# Power_PMIC.net
KiCad netlist of a schematic drawn in Altium Designer
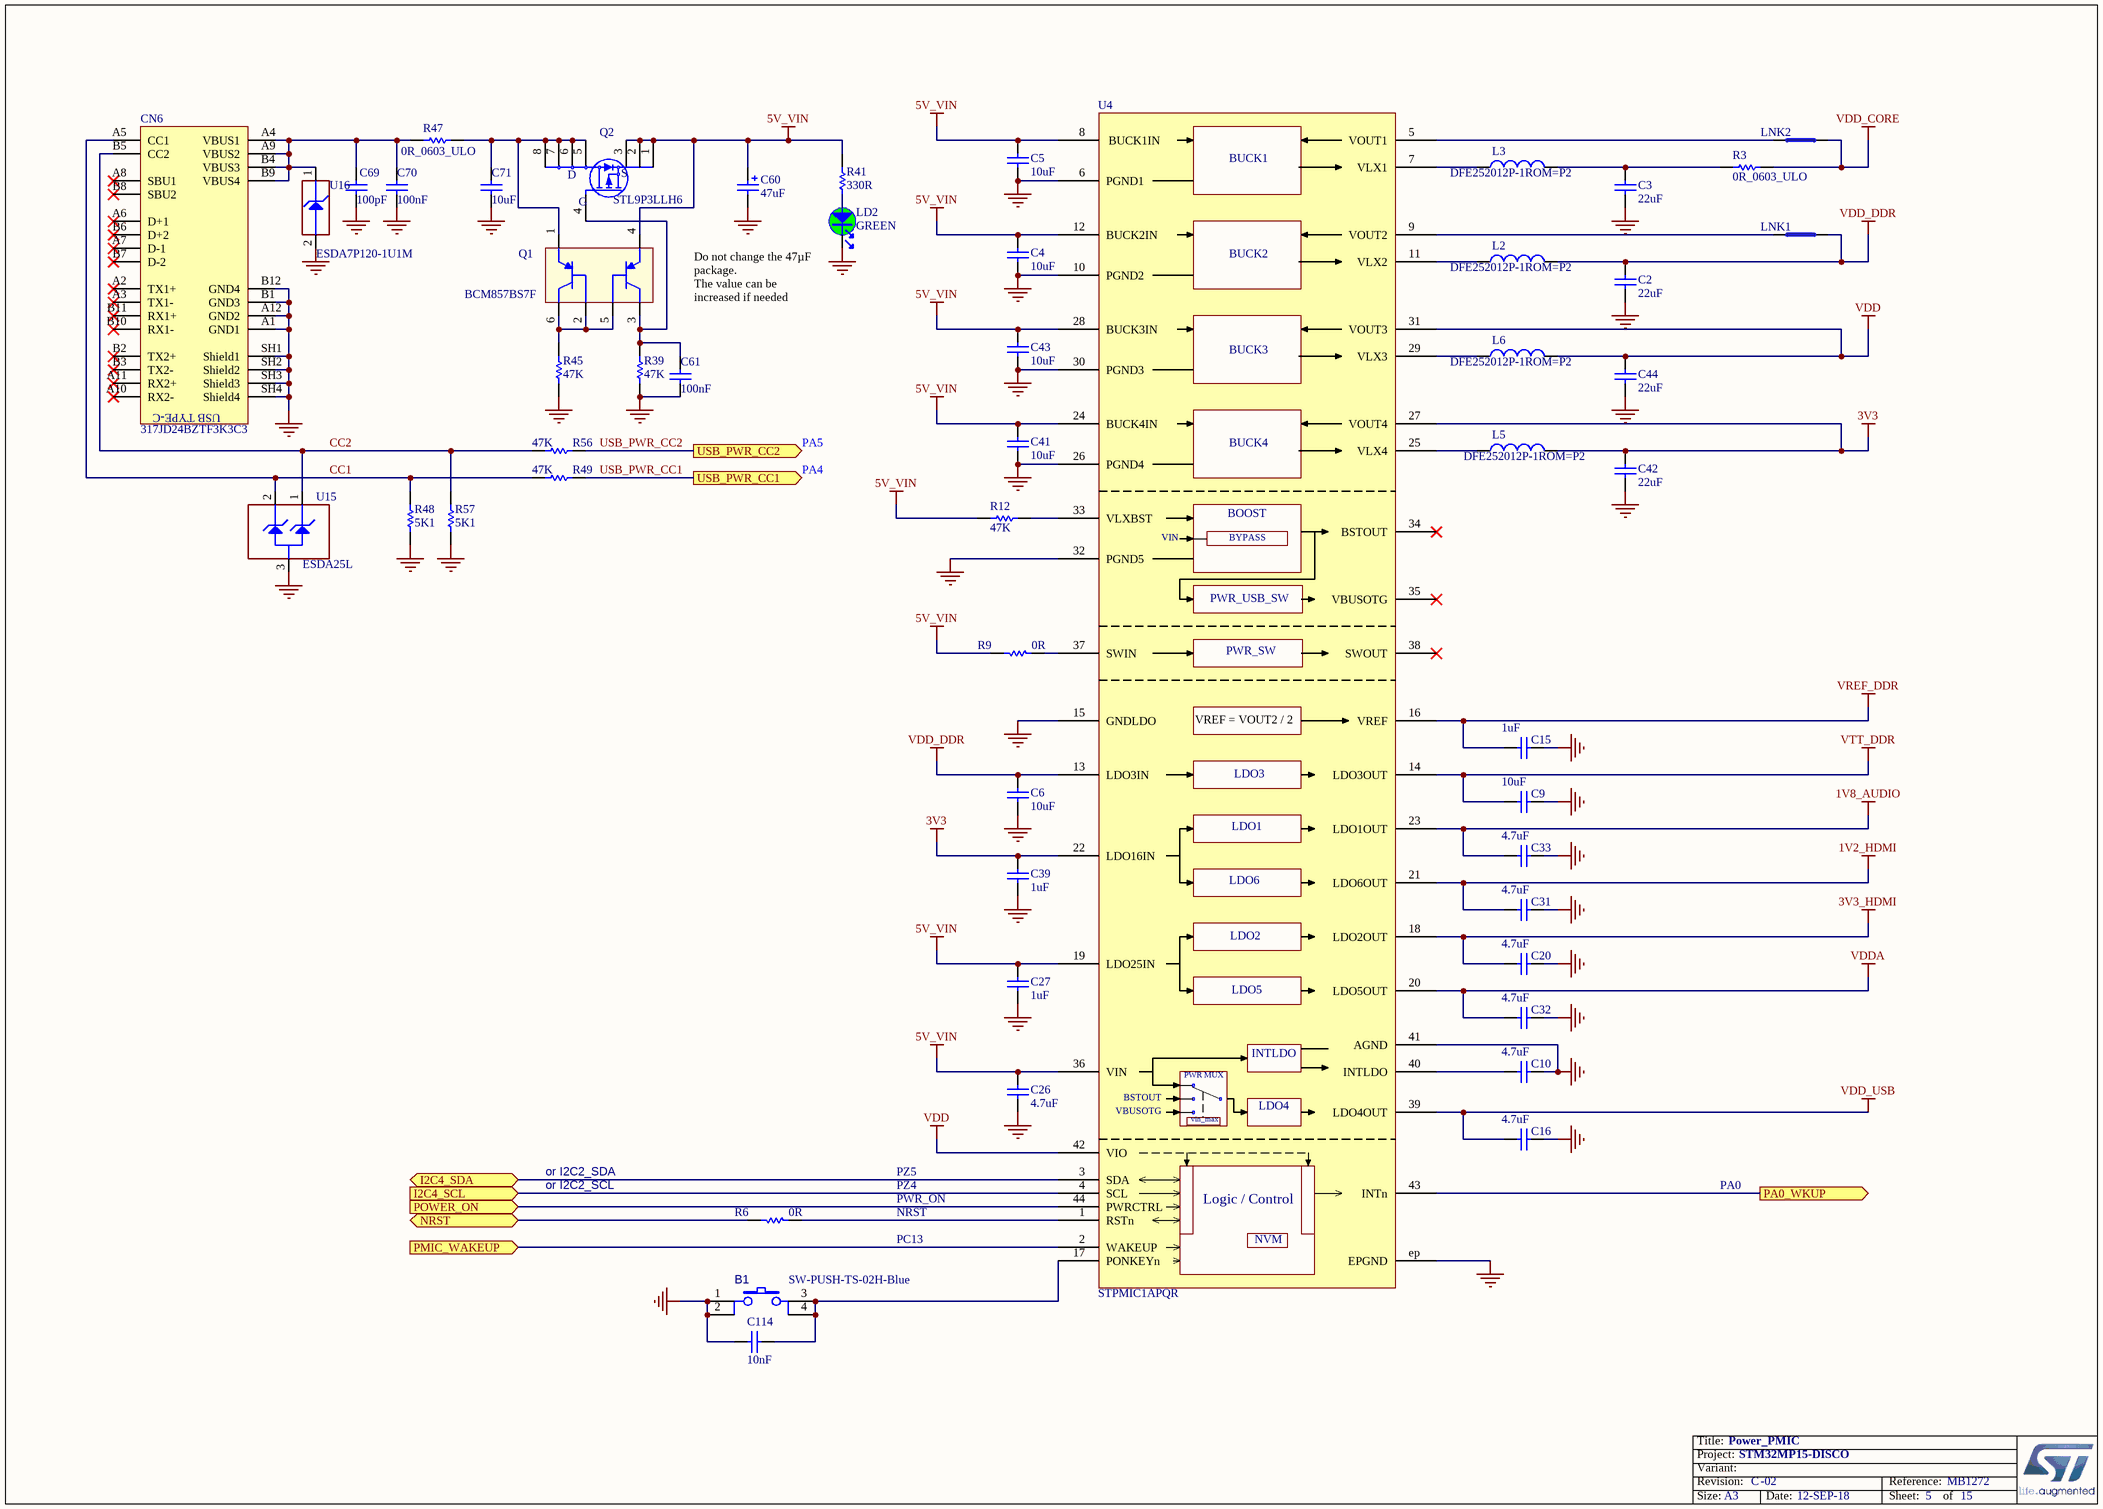
[diagram p0: Power_PMIC.SchDoc]

(export (version "E")
  (design (tool "Eeschema 10.0.6"))
  (components
    (comp (ref "B1")
      (value "SW-PUSH-TS-02H-Blue")
      (footprint "SWI_JIUBABA_C-TS-02H-2-5-B-V-T_R_BLUE")
      (description "Switch HW SMD blue")
      (fields
        (field (name "INTERNAL_PART_NUMBER") "MCD-00172")
        (field (name "MANUFACTURER_PART_NUMBER") "C-TS-02H-2.5-B-V-T/R BLUE")
        (field (name "PROVIDED_BY") "SUBCO")
      )
      (libsource (lib "MCD_PARTS_database") (part "SW-PUSH-TS-02H-Blue"))
    )
    (comp (ref "C2")
      (value "22uF")
      (footprint "C0603")
      (description "Capacitor, MLCC, 22uF, 6V3, X5R, 20%, 0603, T=0,8mm")
      (fields
        (field (name "INTERNAL_PART_NUMBER") "MCD-00100")
        (field (name "MANUFACTURER_PART_NUMBER") "GRM188R60J226MEA0J")
        (field (name "PROVIDED_BY") "SUBCO")
      )
      (libsource (lib "MCD_PARTS_database") (part "Capacitor"))
    )
    (comp (ref "C3")
      (value "22uF")
      (footprint "C0603")
      (description "Capacitor, MLCC, 22uF, 6V3, X5R, 20%, 0603, T=0,8mm")
      (fields
        (field (name "INTERNAL_PART_NUMBER") "MCD-00100")
        (field (name "MANUFACTURER_PART_NUMBER") "GRM188R60J226MEA0J")
        (field (name "PROVIDED_BY") "SUBCO")
      )
      (libsource (lib "MCD_PARTS_database") (part "Capacitor"))
    )
    (comp (ref "C4")
      (value "10uF")
      (footprint "C0603")
      (description "Capacitor, MLCC, 10uF, 10V, X5R, 10%, 0603, T=0,8mm")
      (fields
        (field (name "INTERNAL_PART_NUMBER") "MCD-00099")
        (field (name "MANUFACTURER_PART_NUMBER") "GRM188R61A106KE69D")
        (field (name "PROVIDED_BY") "SUBCO")
      )
      (libsource (lib "MCD_PARTS_database") (part "Capacitor"))
    )
    (comp (ref "C5")
      (value "10uF")
      (footprint "C0603")
      (description "Capacitor, MLCC, 10uF, 10V, X5R, 10%, 0603, T=0,8mm")
      (fields
        (field (name "INTERNAL_PART_NUMBER") "MCD-00099")
        (field (name "MANUFACTURER_PART_NUMBER") "GRM188R61A106KE69D")
        (field (name "PROVIDED_BY") "SUBCO")
      )
      (libsource (lib "MCD_PARTS_database") (part "Capacitor"))
    )
    (comp (ref "C6")
      (value "10uF")
      (footprint "C0603")
      (description "Capacitor, MLCC, 10uF, 10V, X5R, 10%, 0603, T=0,8mm")
      (fields
        (field (name "INTERNAL_PART_NUMBER") "MCD-00099")
        (field (name "MANUFACTURER_PART_NUMBER") "GRM188R61A106KE69D")
        (field (name "PROVIDED_BY") "SUBCO")
      )
      (libsource (lib "MCD_PARTS_database") (part "Capacitor"))
    )
    (comp (ref "C9")
      (value "10uF")
      (footprint "C0603")
      (description "Capacitor, MLCC, 10uF, 10V, X5R, 10%, 0603, T=0,8mm")
      (fields
        (field (name "INTERNAL_PART_NUMBER") "MCD-00099")
        (field (name "MANUFACTURER_PART_NUMBER") "GRM188R61A106KE69D")
        (field (name "PROVIDED_BY") "SUBCO")
      )
      (libsource (lib "MCD_PARTS_database") (part "Capacitor"))
    )
    (comp (ref "C10")
      (value "4.7uF")
      (footprint "C0402")
      (description "Capacitor, MLCC, 4.7uF, 6V3, X5R, 20%, 0402, T=0,5mm")
      (fields
        (field (name "INTERNAL_PART_NUMBER") "MCD-01356")
        (field (name "MANUFACTURER_PART_NUMBER") "GRM155R60J475ME47")
        (field (name "PROVIDED_BY") "SUBCO")
      )
      (libsource (lib "MCD_PARTS_database") (part "Capacitor"))
    )
    (comp (ref "C15")
      (value "1uF")
      (footprint "C0402")
      (description "Capacitor, MLCC, 1uF, 6V3, X5R, 10%, 0402, T=0,5mm")
      (fields
        (field (name "INTERNAL_PART_NUMBER") "MCD-00095")
        (field (name "MANUFACTURER_PART_NUMBER") "GRM155R61E105KA12")
        (field (name "PROVIDED_BY") "SUBCO")
      )
      (libsource (lib "MCD_PARTS_database") (part "Capacitor"))
    )
    (comp (ref "C16")
      (value "4.7uF")
      (footprint "C0402")
      (description "Capacitor, MLCC, 4.7uF, 6V3, X5R, 20%, 0402, T=0,5mm")
      (fields
        (field (name "INTERNAL_PART_NUMBER") "MCD-01356")
        (field (name "MANUFACTURER_PART_NUMBER") "GRM155R60J475ME47")
        (field (name "PROVIDED_BY") "SUBCO")
      )
      (libsource (lib "MCD_PARTS_database") (part "Capacitor"))
    )
    (comp (ref "C20")
      (value "4.7uF")
      (footprint "C0402")
      (description "Capacitor, MLCC, 4.7uF, 6V3, X5R, 20%, 0402, T=0,5mm")
      (fields
        (field (name "INTERNAL_PART_NUMBER") "MCD-01356")
        (field (name "MANUFACTURER_PART_NUMBER") "GRM155R60J475ME47")
        (field (name "PROVIDED_BY") "SUBCO")
      )
      (libsource (lib "MCD_PARTS_database") (part "Capacitor"))
    )
    (comp (ref "C26")
      (value "4.7uF")
      (footprint "C0402")
      (description "Capacitor, MLCC, 4.7uF, 6V3, X5R, 20%, 0402, T=0,5mm")
      (fields
        (field (name "INTERNAL_PART_NUMBER") "MCD-01356")
        (field (name "MANUFACTURER_PART_NUMBER") "GRM155R60J475ME47")
        (field (name "PROVIDED_BY") "SUBCO")
      )
      (libsource (lib "MCD_PARTS_database") (part "Capacitor"))
    )
    (comp (ref "C27")
      (value "1uF")
      (footprint "C0402")
      (description "Capacitor, MLCC, 1uF, 6V3, X5R, 10%, 0402, T=0,5mm")
      (fields
        (field (name "INTERNAL_PART_NUMBER") "MCD-00095")
        (field (name "MANUFACTURER_PART_NUMBER") "GRM155R61E105KA12")
        (field (name "PROVIDED_BY") "SUBCO")
      )
      (libsource (lib "MCD_PARTS_database") (part "Capacitor"))
    )
    (comp (ref "C31")
      (value "4.7uF")
      (footprint "C0402")
      (description "Capacitor, MLCC, 4.7uF, 6V3, X5R, 20%, 0402, T=0,5mm")
      (fields
        (field (name "INTERNAL_PART_NUMBER") "MCD-01356")
        (field (name "MANUFACTURER_PART_NUMBER") "GRM155R60J475ME47")
        (field (name "PROVIDED_BY") "SUBCO")
      )
      (libsource (lib "MCD_PARTS_database") (part "Capacitor"))
    )
    (comp (ref "C32")
      (value "4.7uF")
      (footprint "C0402")
      (description "Capacitor, MLCC, 4.7uF, 6V3, X5R, 20%, 0402, T=0,5mm")
      (fields
        (field (name "INTERNAL_PART_NUMBER") "MCD-01356")
        (field (name "MANUFACTURER_PART_NUMBER") "GRM155R60J475ME47")
        (field (name "PROVIDED_BY") "SUBCO")
      )
      (libsource (lib "MCD_PARTS_database") (part "Capacitor"))
    )
    (comp (ref "C33")
      (value "4.7uF")
      (footprint "C0402")
      (description "Capacitor, MLCC, 4.7uF, 6V3, X5R, 20%, 0402, T=0,5mm")
      (fields
        (field (name "INTERNAL_PART_NUMBER") "MCD-01356")
        (field (name "MANUFACTURER_PART_NUMBER") "GRM155R60J475ME47")
        (field (name "PROVIDED_BY") "SUBCO")
      )
      (libsource (lib "MCD_PARTS_database") (part "Capacitor"))
    )
    (comp (ref "C39")
      (value "1uF")
      (footprint "C0402")
      (description "Capacitor, MLCC, 1uF, 6V3, X5R, 10%, 0402, T=0,5mm")
      (fields
        (field (name "INTERNAL_PART_NUMBER") "MCD-00095")
        (field (name "MANUFACTURER_PART_NUMBER") "GRM155R61E105KA12")
        (field (name "PROVIDED_BY") "SUBCO")
      )
      (libsource (lib "MCD_PARTS_database") (part "Capacitor"))
    )
    (comp (ref "C41")
      (value "10uF")
      (footprint "C0603")
      (description "Capacitor, MLCC, 10uF, 10V, X5R, 10%, 0603, T=0,8mm")
      (fields
        (field (name "INTERNAL_PART_NUMBER") "MCD-00099")
        (field (name "MANUFACTURER_PART_NUMBER") "GRM188R61A106KE69D")
        (field (name "PROVIDED_BY") "SUBCO")
      )
      (libsource (lib "MCD_PARTS_database") (part "Capacitor"))
    )
    (comp (ref "C42")
      (value "22uF")
      (footprint "C0603")
      (description "Capacitor, MLCC, 22uF, 6V3, X5R, 20%, 0603, T=0,8mm")
      (fields
        (field (name "INTERNAL_PART_NUMBER") "MCD-00100")
        (field (name "MANUFACTURER_PART_NUMBER") "GRM188R60J226MEA0J")
        (field (name "PROVIDED_BY") "SUBCO")
      )
      (libsource (lib "MCD_PARTS_database") (part "Capacitor"))
    )
    (comp (ref "C43")
      (value "10uF")
      (footprint "C0603")
      (description "Capacitor, MLCC, 10uF, 10V, X5R, 10%, 0603, T=0,8mm")
      (fields
        (field (name "INTERNAL_PART_NUMBER") "MCD-00099")
        (field (name "MANUFACTURER_PART_NUMBER") "GRM188R61A106KE69D")
        (field (name "PROVIDED_BY") "SUBCO")
      )
      (libsource (lib "MCD_PARTS_database") (part "Capacitor"))
    )
    (comp (ref "C44")
      (value "22uF")
      (footprint "C0603")
      (description "Capacitor, MLCC, 22uF, 6V3, X5R, 20%, 0603, T=0,8mm")
      (fields
        (field (name "INTERNAL_PART_NUMBER") "MCD-00100")
        (field (name "MANUFACTURER_PART_NUMBER") "GRM188R60J226MEA0J")
        (field (name "PROVIDED_BY") "SUBCO")
      )
      (libsource (lib "MCD_PARTS_database") (part "Capacitor"))
    )
    (comp (ref "C60")
      (value "47uF")
      (footprint "CPOL_TAJ-C_2312_H2P6")
      (description "Capacitor, Tantalum, 47uF, 16V, 10%, TypeC")
      (fields
        (field (name "INTERNAL_PART_NUMBER") "MCD-00559")
        (field (name "MANUFACTURER_PART_NUMBER") "TAJC476K016RNJ")
        (field (name "PROVIDED_BY") "SUBCO")
      )
      (libsource (lib "MCD_PARTS_database") (part "Cap_POL_TANA"))
    )
    (comp (ref "C61")
      (value "100nF")
      (footprint "C0402")
      (description "Capacitor,100nF,16V,X7R,10%,0402")
      (fields
        (field (name "INTERNAL_PART_NUMBER") "MCD-00006")
        (field (name "MANUFACTURER_PART_NUMBER") "CC0402KRX7R7BB104")
        (field (name "PROVIDED_BY") "SUBCO")
      )
      (libsource (lib "MCD_PARTS_database") (part "Capacitor"))
    )
    (comp (ref "C69")
      (value "100pF")
      (footprint "C0402")
      (description "Capacitor, MLCC, 100pF, 50V, NPO, 5%, 0402, T=0,5mm")
      (fields
        (field (name "INTERNAL_PART_NUMBER") "MCD-00205")
        (field (name "MANUFACTURER_PART_NUMBER") "CC0402JRNPO9BN101")
        (field (name "PROVIDED_BY") "SUBCO")
      )
      (libsource (lib "MCD_PARTS_database") (part "Capacitor"))
    )
    (comp (ref "C70")
      (value "100nF")
      (footprint "C0402")
      (description "Capacitor,100nF,16V,X7R,10%,0402")
      (fields
        (field (name "INTERNAL_PART_NUMBER") "MCD-00006")
        (field (name "MANUFACTURER_PART_NUMBER") "CC0402KRX7R7BB104")
        (field (name "PROVIDED_BY") "SUBCO")
      )
      (libsource (lib "MCD_PARTS_database") (part "Capacitor"))
    )
    (comp (ref "C71")
      (value "10uF")
      (footprint "C0805")
      (description "Capacitor, MLCC, 10uF, 25V, X5R, 10%, 0805, T=0,85mm")
      (fields
        (field (name "INTERNAL_PART_NUMBER") "MCD-00014")
        (field (name "MANUFACTURER_PART_NUMBER") "CC0805KRX5R8BB106")
        (field (name "PROVIDED_BY") "SUBCO")
      )
      (libsource (lib "MCD_PARTS_database") (part "Capacitor"))
    )
    (comp (ref "C114")
      (value "10nF")
      (footprint "C0402")
      (description "Capacitor, MLCC, 10nF, 16V, X7R, 10%, 0402, T=0.5mm")
      (fields
        (field (name "INTERNAL_PART_NUMBER") "MCD-00011")
        (field (name "MANUFACTURER_PART_NUMBER") "CC0402KRX7R7BB103")
        (field (name "PROVIDED_BY") "SUBCO")
      )
      (libsource (lib "MCD_PARTS_database") (part "Capacitor"))
    )
    (comp (ref "CN6")
      (value "317JD24BZTF3K3C3")
      (footprint "CON_USB-TYPEC_COXOC_317JD24BZTF3K3C3")
      (description "USB tyce C certified receptacle for 1.6mm pcb height")
      (fields
        (field (name "INTERNAL_PART_NUMBER") "MCD-01108")
        (field (name "MANUFACTURER") "CHANT SINCERE (COXOC)")
        (field (name "PROVIDED_BY") "SUBCO")
      )
      (libsource (lib "MCD_PARTS_database") (part "USB_TYPE_C_Receptacle_317JD24BZTF3K3C3"))
    )
    (comp (ref "L2")
      (value "IND_1uH_42mohm_3.2A")
      (footprint "IND_2520_TOKO_DFE252012P")
      (description "Power Inductor ,1µH,4.3A max,+-20%,0.042ohm,2520")
      (fields
        (field (name "INTERNAL_PART_NUMBER") "MCD-01122")
        (field (name "MANUFACTURER_PART_NUMBER") "DFE252012P-1ROM=P2")
        (field (name "MANUFACTURER") "MURATA")
        (field (name "PROVIDED_BY") "SUBCO")
      )
      (libsource (lib "MCD_PARTS_database") (part "IND_1uH_42mohm_3.2A"))
    )
    (comp (ref "L3")
      (value "IND_1uH_42mohm_3.2A")
      (footprint "IND_2520_TOKO_DFE252012P")
      (description "Power Inductor ,1µH,4.3A max,+-20%,0.042ohm,2520")
      (fields
        (field (name "INTERNAL_PART_NUMBER") "MCD-01122")
        (field (name "MANUFACTURER_PART_NUMBER") "DFE252012P-1ROM=P2")
        (field (name "MANUFACTURER") "MURATA")
        (field (name "PROVIDED_BY") "SUBCO")
      )
      (libsource (lib "MCD_PARTS_database") (part "IND_1uH_42mohm_3.2A"))
    )
    (comp (ref "L5")
      (value "IND_1uH_42mohm_3.2A")
      (footprint "IND_2520_TOKO_DFE252012P")
      (description "Power Inductor ,1µH,4.3A max,+-20%,0.042ohm,2520")
      (fields
        (field (name "INTERNAL_PART_NUMBER") "MCD-01122")
        (field (name "MANUFACTURER_PART_NUMBER") "DFE252012P-1ROM=P2")
        (field (name "MANUFACTURER") "MURATA")
        (field (name "PROVIDED_BY") "SUBCO")
      )
      (libsource (lib "MCD_PARTS_database") (part "IND_1uH_42mohm_3.2A"))
    )
    (comp (ref "L6")
      (value "IND_1uH_42mohm_3.2A")
      (footprint "IND_2520_TOKO_DFE252012P")
      (description "Power Inductor ,1µH,4.3A max,+-20%,0.042ohm,2520")
      (fields
        (field (name "INTERNAL_PART_NUMBER") "MCD-01122")
        (field (name "MANUFACTURER_PART_NUMBER") "DFE252012P-1ROM=P2")
        (field (name "MANUFACTURER") "MURATA")
        (field (name "PROVIDED_BY") "SUBCO")
      )
      (libsource (lib "MCD_PARTS_database") (part "IND_1uH_42mohm_3.2A"))
    )
    (comp (ref "LD2")
      (value "GREEN")
      (footprint "LED_0603_GREEN")
      (description "LED, Green, 0603")
      (fields
        (field (name "INTERNAL_PART_NUMBER") "MCD-00050")
        (field (name "MANUFACTURER_PART_NUMBER") "19-213SYGC/S530-E2/TR8")
        (field (name "PROVIDED_BY") "SUBCO")
      )
      (libsource (lib "MCD_PARTS_database") (part "LED_green"))
    )
    (comp (ref "LNK1")
      (value "link_200")
      (footprint "LINK200")
      (description "link 0.2mm")
      (libsource (lib "MCD_Temp_LBE") (part "link_200"))
    )
    (comp (ref "LNK2")
      (value "link_200")
      (footprint "LINK200")
      (description "link 0.2mm")
      (libsource (lib "MCD_Temp_LBE") (part "link_200"))
    )
    (comp (ref "Q1")
      (value "BCM857BS7F")
      (footprint "DIO_SOT363")
      (description "Transistor 45V Matched Pair PNP small Signal transistor in SOT363")
      (fields
        (field (name "INTERNAL_PART_NUMBER") "MCD-01120")
        (field (name "MANUFACTURER") "DIODES_INC")
        (field (name "PROVIDED_BY") "SUBCO")
      )
      (libsource (lib "MCD_PARTS_database") (part "BCM857BS"))
    )
    (comp (ref "Q2")
      (value "STL9P3LLH6")
      (footprint "MOS_POWERFLAT_3P3X3P3_P065")
      (description "Power Mosfet, P-channel,VDS -30V,RDS 12mohm typ,ID -9A")
      (fields
        (field (name "INTERNAL_PART_NUMBER") "MCD-01126")
        (field (name "MANUFACTURER") "STMICROELECTRONICS")
        (field (name "PROVIDED_BY") "SUBCO with ST control")
      )
      (libsource (lib "MCD_PARTS_database") (part "STL9P3LLH6"))
    )
    (comp (ref "R3")
      (value "0R_0603_ULO")
      (footprint "R0603")
      (description "Resistor,0R,0603,ULO")
      (fields
        (field (name "INTERNAL_PART_NUMBER") "MCD-00181")
        (field (name "MANUFACTURER_PART_NUMBER") "PMR03EZPJ000")
        (field (name "PROVIDED_BY") "SUBCO")
      )
      (libsource (lib "MCD_PARTS_database") (part "Resistor"))
    )
    (comp (ref "R6")
      (value "0R")
      (footprint "R0402")
      (description "Resistor,0R,0402,5%,1/16W")
      (fields
        (field (name "INTERNAL_PART_NUMBER") "MCD-00052")
        (field (name "MANUFACTURER_PART_NUMBER") "RC0402JR-070RL")
        (field (name "PROVIDED_BY") "SUBCO")
      )
      (libsource (lib "MCD_PARTS_database") (part "Resistor"))
    )
    (comp (ref "R9")
      (value "0R")
      (footprint "R0402")
      (description "Resistor,0R,0402,5%,1/16W")
      (fields
        (field (name "INTERNAL_PART_NUMBER") "MCD-00052")
        (field (name "MANUFACTURER_PART_NUMBER") "RC0402JR-070RL")
        (field (name "PROVIDED_BY") "SUBCO")
      )
      (libsource (lib "MCD_PARTS_database") (part "Resistor"))
    )
    (comp (ref "R12")
      (value "47K")
      (footprint "R0402")
      (description "Resistor,47K,0402,1%,1/16W")
      (fields
        (field (name "INTERNAL_PART_NUMBER") "MCD-00063")
        (field (name "MANUFACTURER_PART_NUMBER") "RC0402FR-0747KL")
        (field (name "PROVIDED_BY") "SUBCO")
      )
      (libsource (lib "MCD_PARTS_database") (part "Resistor"))
    )
    (comp (ref "R39")
      (value "47K")
      (footprint "R0402")
      (description "Resistor,47K,0402,1%,1/16W")
      (fields
        (field (name "INTERNAL_PART_NUMBER") "MCD-00063")
        (field (name "MANUFACTURER_PART_NUMBER") "RC0402FR-0747KL")
        (field (name "PROVIDED_BY") "SUBCO")
      )
      (libsource (lib "MCD_PARTS_database") (part "Resistor"))
    )
    (comp (ref "R41")
      (value "330R")
      (footprint "R0402")
      (description "Resistor,330R,0402,1%,1/16W")
      (fields
        (field (name "INTERNAL_PART_NUMBER") "MCD-00062")
        (field (name "MANUFACTURER_PART_NUMBER") "RC0402FR-07330RL")
        (field (name "PROVIDED_BY") "SUBCO")
      )
      (libsource (lib "MCD_PARTS_database") (part "Resistor"))
    )
    (comp (ref "R45")
      (value "47K")
      (footprint "R0402")
      (description "Resistor,47K,0402,1%,1/16W")
      (fields
        (field (name "INTERNAL_PART_NUMBER") "MCD-00063")
        (field (name "MANUFACTURER_PART_NUMBER") "RC0402FR-0747KL")
        (field (name "PROVIDED_BY") "SUBCO")
      )
      (libsource (lib "MCD_PARTS_database") (part "Resistor"))
    )
    (comp (ref "R47")
      (value "0R_0603_ULO")
      (footprint "R0603")
      (description "Resistor,0R,0603,ULO")
      (fields
        (field (name "INTERNAL_PART_NUMBER") "MCD-00181")
        (field (name "MANUFACTURER_PART_NUMBER") "PMR03EZPJ000")
        (field (name "PROVIDED_BY") "SUBCO")
      )
      (libsource (lib "MCD_PARTS_database") (part "Resistor"))
    )
    (comp (ref "R48")
      (value "5K1")
      (footprint "R0402")
      (description "Resistor,5K1,0402,1%,1/16W")
      (fields
        (field (name "INTERNAL_PART_NUMBER") "MCD-00333")
        (field (name "MANUFACTURER_PART_NUMBER") "RC0402FR-075K1L")
        (field (name "PROVIDED_BY") "SUBCO")
      )
      (libsource (lib "MCD_PARTS_database") (part "Resistor"))
    )
    (comp (ref "R49")
      (value "47K")
      (footprint "R0402")
      (description "Resistor,47K,0402,1%,1/16W")
      (fields
        (field (name "INTERNAL_PART_NUMBER") "MCD-00063")
        (field (name "MANUFACTURER_PART_NUMBER") "RC0402FR-0747KL")
        (field (name "PROVIDED_BY") "SUBCO")
      )
      (libsource (lib "MCD_PARTS_database") (part "Resistor"))
    )
    (comp (ref "R56")
      (value "47K")
      (footprint "R0402")
      (description "Resistor,47K,0402,1%,1/16W")
      (fields
        (field (name "INTERNAL_PART_NUMBER") "MCD-00063")
        (field (name "MANUFACTURER_PART_NUMBER") "RC0402FR-0747KL")
        (field (name "PROVIDED_BY") "SUBCO")
      )
      (libsource (lib "MCD_PARTS_database") (part "Resistor"))
    )
    (comp (ref "R57")
      (value "5K1")
      (footprint "R0402")
      (description "Resistor,5K1,0402,1%,1/16W")
      (fields
        (field (name "INTERNAL_PART_NUMBER") "MCD-00333")
        (field (name "MANUFACTURER_PART_NUMBER") "RC0402FR-075K1L")
        (field (name "PROVIDED_BY") "SUBCO")
      )
      (libsource (lib "MCD_PARTS_database") (part "Resistor"))
    )
    (comp (ref "U4")
      (value "STPMIC1APQR")
      (footprint "ICC_WFQFN44-EPAD_5X6_P040")
      (fields
        (field (name "INTERNAL_PART_NUMBER") "MCD-01650")
        (field (name "MANUFACTURER") "STMICROELECTRONICS")
        (field (name "Comment") "STPMU1")
        (field (name "PROVIDED_BY") "SUBCO with ST control")
      )
      (libsource (lib "MCD_PARTS_database") (part "STPMU1"))
    )
    (comp (ref "U15")
      (value "ESDA25L")
      (footprint "ESD_SOT23")
      (description "DUAL TRANSIL ARRAY FOR ESD PROTECTION")
      (fields
        (field (name "INTERNAL_PART_NUMBER") "MCD-01125")
        (field (name "MANUFACTURER") "STMICROELECTRONICS")
        (field (name "PROVIDED_BY") "SUBCO with ST control")
      )
      (libsource (lib "MCD_PARTS_database") (part "ESDA25L"))
    )
    (comp (ref "U16")
      (value "ESDA7P120-1U1M")
      (footprint "ESD_QFN1610_2N_1K_2A")
      (description "High power transient voltage suppressor")
      (fields
        (field (name "INTERNAL_PART_NUMBER") "MCD-01026")
        (field (name "MANUFACTURER") "STMICROELECTRONICS")
        (field (name "PROVIDED_BY") "SUBCO with ST control")
      )
      (libsource (lib "MCD_PARTS_database") (part "ESD-TRANSIL"))
    )
  )
  (nets
    (net (code "1") (name "/CC1") (class "Default")
      (node (ref "CN6") (pin "A5") (pinfunction "CC1_A5") (pintype "passive"))
      (node (ref "R48") (pin "2") (pinfunction "2_2") (pintype "passive"))
      (node (ref "R49") (pin "1") (pinfunction "1_1") (pintype "passive"))
      (node (ref "U15") (pin "2") (pinfunction "IO2_2") (pintype "passive"))
    )
    (net (code "2") (name "/CC2") (class "Default")
      (node (ref "CN6") (pin "B5") (pinfunction "CC2_B5") (pintype "passive"))
      (node (ref "R56") (pin "1") (pinfunction "1_1") (pintype "passive"))
      (node (ref "R57") (pin "2") (pinfunction "2_2") (pintype "passive"))
      (node (ref "U15") (pin "1") (pinfunction "IO1_1") (pintype "passive"))
    )
    (net (code "3") (name "/I2C4_SCL") (class "Default")
      (node (ref "U4") (pin "4") (pinfunction "SCL_4") (pintype "passive"))
    )
    (net (code "4") (name "/I2C4_SDA") (class "Default")
      (node (ref "U4") (pin "3") (pinfunction "SDA_3") (pintype "passive"))
    )
    (net (code "5") (name "/NRST") (class "Default")
      (node (ref "R6") (pin "1") (pinfunction "1_1") (pintype "passive"))
    )
    (net (code "6") (name "/PA0_WKUP") (class "Default")
      (node (ref "U4") (pin "43") (pinfunction "INTn_43") (pintype "passive"))
    )
    (net (code "7") (name "/PMIC_WAKEUP") (class "Default")
      (node (ref "U4") (pin "2") (pinfunction "WAKEUP_2") (pintype "passive"))
    )
    (net (code "8") (name "/POWER_ON") (class "Default")
      (node (ref "U4") (pin "44") (pinfunction "PWRCTRL_44") (pintype "passive"))
    )
    (net (code "9") (name "/USB_PWR_CC1") (class "Default")
      (node (ref "R49") (pin "2") (pinfunction "2_2") (pintype "passive"))
    )
    (net (code "10") (name "/USB_PWR_CC2") (class "Default")
      (node (ref "R56") (pin "2") (pinfunction "2_2") (pintype "passive"))
    )
    (net (code "11") (name "1V2_HDMI") (class "Default")
      (node (ref "C31") (pin "2") (pinfunction "2_2") (pintype "passive"))
      (node (ref "U4") (pin "21") (pinfunction "LDO6OUT_21") (pintype "passive"))
    )
    (net (code "12") (name "1V8_AUDIO") (class "Default")
      (node (ref "C33") (pin "2") (pinfunction "2_2") (pintype "passive"))
      (node (ref "U4") (pin "23") (pinfunction "LDO1OUT_23") (pintype "passive"))
    )
    (net (code "13") (name "3V3") (class "Default")
      (node (ref "C39") (pin "2") (pinfunction "2_2") (pintype "passive"))
      (node (ref "C42") (pin "2") (pinfunction "2_2") (pintype "passive"))
      (node (ref "L5") (pin "2") (pinfunction "2_2") (pintype "passive"))
      (node (ref "U4") (pin "22") (pinfunction "LDO16IN_22") (pintype "passive"))
      (node (ref "U4") (pin "27") (pinfunction "VOUT4_27") (pintype "passive"))
    )
    (net (code "14") (name "3V3_HDMI") (class "Default")
      (node (ref "C20") (pin "2") (pinfunction "2_2") (pintype "passive"))
      (node (ref "U4") (pin "18") (pinfunction "LDO2OUT_18") (pintype "passive"))
    )
    (net (code "15") (name "5V_VIN") (class "Default")
      (node (ref "C26") (pin "2") (pinfunction "2_2") (pintype "passive"))
      (node (ref "C27") (pin "2") (pinfunction "2_2") (pintype "passive"))
      (node (ref "C4") (pin "2") (pinfunction "2_2") (pintype "passive"))
      (node (ref "C41") (pin "2") (pinfunction "2_2") (pintype "passive"))
      (node (ref "C43") (pin "2") (pinfunction "2_2") (pintype "passive"))
      (node (ref "C5") (pin "2") (pinfunction "2_2") (pintype "passive"))
      (node (ref "C60") (pin "1") (pinfunction "1_1") (pintype "passive"))
      (node (ref "Q1") (pin "4") (pinfunction "E2_4") (pintype "passive"))
      (node (ref "Q2") (pin "1") (pinfunction "S_1") (pintype "passive"))
      (node (ref "Q2") (pin "2") (pinfunction "S_2") (pintype "passive"))
      (node (ref "Q2") (pin "3") (pinfunction "S_3") (pintype "passive"))
      (node (ref "R12") (pin "2") (pinfunction "2_2") (pintype "passive"))
      (node (ref "R41") (pin "2") (pinfunction "2_2") (pintype "passive"))
      (node (ref "R9") (pin "1") (pinfunction "1_1") (pintype "passive"))
      (node (ref "U4") (pin "12") (pinfunction "BUCK2IN_12") (pintype "passive"))
      (node (ref "U4") (pin "19") (pinfunction "LDO25IN_19") (pintype "passive"))
      (node (ref "U4") (pin "24") (pinfunction "BUCK4IN_24") (pintype "passive"))
      (node (ref "U4") (pin "28") (pinfunction "BUCK3IN_28") (pintype "passive"))
      (node (ref "U4") (pin "36") (pinfunction "VIN_36") (pintype "passive"))
      (node (ref "U4") (pin "8") (pinfunction "BUCK1IN_8") (pintype "passive"))
    )
    (net (code "16") (name "GND") (class "Default")
      (node (ref "B1") (pin "1") (pinfunction "1_1") (pintype "passive"))
      (node (ref "B1") (pin "2") (pinfunction "2_2") (pintype "passive"))
      (node (ref "C10") (pin "2") (pinfunction "2_2") (pintype "passive"))
      (node (ref "C114") (pin "1") (pinfunction "1_1") (pintype "passive"))
      (node (ref "C15") (pin "1") (pinfunction "1_1") (pintype "passive"))
      (node (ref "C16") (pin "1") (pinfunction "1_1") (pintype "passive"))
      (node (ref "C2") (pin "1") (pinfunction "1_1") (pintype "passive"))
      (node (ref "C20") (pin "1") (pinfunction "1_1") (pintype "passive"))
      (node (ref "C26") (pin "1") (pinfunction "1_1") (pintype "passive"))
      (node (ref "C27") (pin "1") (pinfunction "1_1") (pintype "passive"))
      (node (ref "C3") (pin "1") (pinfunction "1_1") (pintype "passive"))
      (node (ref "C31") (pin "1") (pinfunction "1_1") (pintype "passive"))
      (node (ref "C32") (pin "1") (pinfunction "1_1") (pintype "passive"))
      (node (ref "C33") (pin "1") (pinfunction "1_1") (pintype "passive"))
      (node (ref "C39") (pin "1") (pinfunction "1_1") (pintype "passive"))
      (node (ref "C4") (pin "1") (pinfunction "1_1") (pintype "passive"))
      (node (ref "C41") (pin "1") (pinfunction "1_1") (pintype "passive"))
      (node (ref "C42") (pin "1") (pinfunction "1_1") (pintype "passive"))
      (node (ref "C43") (pin "1") (pinfunction "1_1") (pintype "passive"))
      (node (ref "C44") (pin "1") (pinfunction "1_1") (pintype "passive"))
      (node (ref "C5") (pin "1") (pinfunction "1_1") (pintype "passive"))
      (node (ref "C6") (pin "1") (pinfunction "1_1") (pintype "passive"))
      (node (ref "C60") (pin "2") (pinfunction "2_2") (pintype "passive"))
      (node (ref "C61") (pin "2") (pinfunction "2_2") (pintype "passive"))
      (node (ref "C69") (pin "1") (pinfunction "1_1") (pintype "passive"))
      (node (ref "C70") (pin "2") (pinfunction "2_2") (pintype "passive"))
      (node (ref "C71") (pin "1") (pinfunction "1_1") (pintype "passive"))
      (node (ref "C9") (pin "1") (pinfunction "1_1") (pintype "passive"))
      (node (ref "CN6") (pin "A1") (pinfunction "GND1_A1") (pintype "passive"))
      (node (ref "CN6") (pin "A12") (pinfunction "GND2_A12") (pintype "passive"))
      (node (ref "CN6") (pin "B1") (pinfunction "GND3_B1") (pintype "passive"))
      (node (ref "CN6") (pin "B12") (pinfunction "GND4_B12") (pintype "passive"))
      (node (ref "CN6") (pin "SH1") (pinfunction "Shield1_SH1") (pintype "passive"))
      (node (ref "CN6") (pin "SH2") (pinfunction "Shield2_SH2") (pintype "passive"))
      (node (ref "CN6") (pin "SH3") (pinfunction "Shield3_SH3") (pintype "passive"))
      (node (ref "CN6") (pin "SH4") (pinfunction "Shield4_SH4") (pintype "passive"))
      (node (ref "LD2") (pin "2") (pintype "passive"))
      (node (ref "R39") (pin "1") (pinfunction "1_1") (pintype "passive"))
      (node (ref "R45") (pin "1") (pinfunction "1_1") (pintype "passive"))
      (node (ref "R48") (pin "1") (pinfunction "1_1") (pintype "passive"))
      (node (ref "R57") (pin "1") (pinfunction "1_1") (pintype "passive"))
      (node (ref "U15") (pin "3") (pinfunction "GND_3") (pintype "passive"))
      (node (ref "U16") (pin "2") (pinfunction "GND_2") (pintype "passive"))
      (node (ref "U4") (pin "10") (pinfunction "PGND2_10") (pintype "passive"))
      (node (ref "U4") (pin "15") (pinfunction "GNDLDO_15") (pintype "passive"))
      (node (ref "U4") (pin "26") (pinfunction "PGND4_26") (pintype "passive"))
      (node (ref "U4") (pin "30") (pinfunction "PGND3_30") (pintype "passive"))
      (node (ref "U4") (pin "32") (pinfunction "PGND5_32") (pintype "passive"))
      (node (ref "U4") (pin "41") (pinfunction "AGND_41") (pintype "passive"))
      (node (ref "U4") (pin "6") (pinfunction "PGND1_6") (pintype "passive"))
      (node (ref "U4") (pin "ep") (pinfunction "EPGND_ep") (pintype "passive"))
    )
    (net (code "17") (name "Net-(C3-Pad2)") (class "Default")
      (node (ref "C3") (pin "2") (pinfunction "2_2") (pintype "passive"))
      (node (ref "L3") (pin "2") (pinfunction "2_2") (pintype "passive"))
      (node (ref "R3") (pin "1") (pinfunction "1_1") (pintype "passive"))
    )
    (net (code "18") (name "Net-(CN6-VBUS1)") (class "Default")
      (node (ref "C69") (pin "2") (pinfunction "2_2") (pintype "passive"))
      (node (ref "C70") (pin "1") (pinfunction "1_1") (pintype "passive"))
      (node (ref "CN6") (pin "A4") (pinfunction "VBUS1_A4") (pintype "passive"))
      (node (ref "CN6") (pin "A9") (pinfunction "VBUS2_A9") (pintype "passive"))
      (node (ref "CN6") (pin "B4") (pinfunction "VBUS3_B4") (pintype "passive"))
      (node (ref "CN6") (pin "B9") (pinfunction "VBUS4_B9") (pintype "passive"))
      (node (ref "R47") (pin "1") (pinfunction "1_1") (pintype "passive"))
      (node (ref "U16") (pin "1") (pinfunction "IO1_1") (pintype "passive"))
    )
    (net (code "19") (name "Net-(LD2-Pad1)") (class "Default")
      (node (ref "LD2") (pin "1") (pintype "passive"))
      (node (ref "R41") (pin "1") (pinfunction "1_1") (pintype "passive"))
    )
    (net (code "20") (name "Net-(Q1-B1)") (class "Default")
      (node (ref "Q1") (pin "2") (pinfunction "B1_2") (pintype "passive"))
      (node (ref "Q1") (pin "5") (pinfunction "B2_5") (pintype "passive"))
      (node (ref "Q1") (pin "6") (pinfunction "C1_6") (pintype "passive"))
      (node (ref "R45") (pin "2") (pinfunction "2_2") (pintype "passive"))
    )
    (net (code "21") (name "Net-(Q1-C2)") (class "Default")
      (node (ref "C61") (pin "1") (pinfunction "1_1") (pintype "passive"))
      (node (ref "Q1") (pin "3") (pinfunction "C2_3") (pintype "passive"))
      (node (ref "Q2") (pin "4") (pinfunction "G_4") (pintype "passive"))
      (node (ref "R39") (pin "2") (pinfunction "2_2") (pintype "passive"))
    )
    (net (code "22") (name "Net-(Q1-E1)") (class "Default")
      (node (ref "C71") (pin "2") (pinfunction "2_2") (pintype "passive"))
      (node (ref "Q1") (pin "1") (pinfunction "E1_1") (pintype "passive"))
      (node (ref "Q2") (pin "5") (pinfunction "D_5") (pintype "passive"))
      (node (ref "Q2") (pin "6") (pinfunction "D_6") (pintype "passive"))
      (node (ref "Q2") (pin "7") (pinfunction "D_7") (pintype "passive"))
      (node (ref "Q2") (pin "8") (pinfunction "D_8") (pintype "passive"))
      (node (ref "R47") (pin "2") (pinfunction "2_2") (pintype "passive"))
    )
    (net (code "23") (name "Net-(U4-INTLDO)") (class "Default")
      (node (ref "C10") (pin "1") (pinfunction "1_1") (pintype "passive"))
      (node (ref "U4") (pin "40") (pinfunction "INTLDO_40") (pintype "passive"))
    )
    (net (code "24") (name "Net-(U4-PONKEYn)") (class "Default")
      (node (ref "B1") (pin "3") (pinfunction "3_3") (pintype "passive"))
      (node (ref "B1") (pin "4") (pinfunction "4_4") (pintype "passive"))
      (node (ref "C114") (pin "2") (pinfunction "2_2") (pintype "passive"))
      (node (ref "U4") (pin "17") (pinfunction "PONKEYn_17") (pintype "passive"))
    )
    (net (code "25") (name "Net-(U4-RSTn)") (class "Default")
      (node (ref "R6") (pin "2") (pinfunction "2_2") (pintype "passive"))
      (node (ref "U4") (pin "1") (pinfunction "RSTn_1") (pintype "passive"))
    )
    (net (code "26") (name "Net-(U4-SWIN)") (class "Default")
      (node (ref "R9") (pin "2") (pinfunction "2_2") (pintype "passive"))
      (node (ref "U4") (pin "37") (pinfunction "SWIN_37") (pintype "passive"))
    )
    (net (code "27") (name "Net-(U4-VLX1)") (class "Default")
      (node (ref "L3") (pin "1") (pinfunction "1_1") (pintype "passive"))
      (node (ref "U4") (pin "7") (pinfunction "VLX1_7") (pintype "passive"))
    )
    (net (code "28") (name "Net-(U4-VLX2)") (class "Default")
      (node (ref "L2") (pin "1") (pinfunction "1_1") (pintype "passive"))
      (node (ref "U4") (pin "11") (pinfunction "VLX2_11") (pintype "passive"))
    )
    (net (code "29") (name "Net-(U4-VLX3)") (class "Default")
      (node (ref "L6") (pin "1") (pinfunction "1_1") (pintype "passive"))
      (node (ref "U4") (pin "29") (pinfunction "VLX3_29") (pintype "passive"))
    )
    (net (code "30") (name "Net-(U4-VLX4)") (class "Default")
      (node (ref "L5") (pin "1") (pinfunction "1_1") (pintype "passive"))
      (node (ref "U4") (pin "25") (pinfunction "VLX4_25") (pintype "passive"))
    )
    (net (code "31") (name "Net-(U4-VLXBST)") (class "Default")
      (node (ref "R12") (pin "1") (pinfunction "1_1") (pintype "passive"))
      (node (ref "U4") (pin "33") (pinfunction "VLXBST_33") (pintype "passive"))
    )
    (net (code "32") (name "Net-(U4-VOUT1)") (class "Default")
      (node (ref "LNK2") (pin "1") (pinfunction "1_1") (pintype "passive"))
      (node (ref "U4") (pin "5") (pinfunction "VOUT1_5") (pintype "passive"))
    )
    (net (code "33") (name "Net-(U4-VOUT2)") (class "Default")
      (node (ref "LNK1") (pin "1") (pinfunction "1_1") (pintype "passive"))
      (node (ref "U4") (pin "9") (pinfunction "VOUT2_9") (pintype "passive"))
    )
    (net (code "34") (name "VDD") (class "Default")
      (node (ref "C44") (pin "2") (pinfunction "2_2") (pintype "passive"))
      (node (ref "L6") (pin "2") (pinfunction "2_2") (pintype "passive"))
      (node (ref "U4") (pin "31") (pinfunction "VOUT3_31") (pintype "passive"))
      (node (ref "U4") (pin "42") (pinfunction "VIO_42") (pintype "passive"))
    )
    (net (code "35") (name "VDDA") (class "Default")
      (node (ref "C32") (pin "2") (pinfunction "2_2") (pintype "passive"))
      (node (ref "U4") (pin "20") (pinfunction "LDO5OUT_20") (pintype "passive"))
    )
    (net (code "36") (name "VDD_CORE") (class "Default")
      (node (ref "LNK2") (pin "2") (pinfunction "2_2") (pintype "passive"))
      (node (ref "R3") (pin "2") (pinfunction "2_2") (pintype "passive"))
    )
    (net (code "37") (name "VDD_DDR") (class "Default")
      (node (ref "C2") (pin "2") (pinfunction "2_2") (pintype "passive"))
      (node (ref "C6") (pin "2") (pinfunction "2_2") (pintype "passive"))
      (node (ref "L2") (pin "2") (pinfunction "2_2") (pintype "passive"))
      (node (ref "LNK1") (pin "2") (pinfunction "2_2") (pintype "passive"))
      (node (ref "U4") (pin "13") (pinfunction "LDO3IN_13") (pintype "passive"))
    )
    (net (code "38") (name "VDD_USB") (class "Default")
      (node (ref "C16") (pin "2") (pinfunction "2_2") (pintype "passive"))
      (node (ref "U4") (pin "39") (pinfunction "LDO4OUT_39") (pintype "passive"))
    )
    (net (code "39") (name "VREF_DDR") (class "Default")
      (node (ref "C15") (pin "2") (pinfunction "2_2") (pintype "passive"))
      (node (ref "U4") (pin "16") (pinfunction "VREF_16") (pintype "passive"))
    )
    (net (code "40") (name "VTT_DDR") (class "Default")
      (node (ref "C9") (pin "2") (pinfunction "2_2") (pintype "passive"))
      (node (ref "U4") (pin "14") (pinfunction "LDO3OUT_14") (pintype "passive"))
    )
    (net (code "41") (name "unconnected-(CN6-D+1-PadA6)") (class "Default")
      (node (ref "CN6") (pin "A6") (pinfunction "D+1_A6") (pintype "passive+no_connect"))
    )
    (net (code "42") (name "unconnected-(CN6-D+2-PadB6)") (class "Default")
      (node (ref "CN6") (pin "B6") (pinfunction "D+2_B6") (pintype "passive+no_connect"))
    )
    (net (code "43") (name "unconnected-(CN6-D-1-PadA7)") (class "Default")
      (node (ref "CN6") (pin "A7") (pinfunction "D-1_A7") (pintype "passive+no_connect"))
    )
    (net (code "44") (name "unconnected-(CN6-D-2-PadB7)") (class "Default")
      (node (ref "CN6") (pin "B7") (pinfunction "D-2_B7") (pintype "passive+no_connect"))
    )
    (net (code "45") (name "unconnected-(CN6-RX1+-PadB11)") (class "Default")
      (node (ref "CN6") (pin "B11") (pinfunction "RX1+_B11") (pintype "passive+no_connect"))
    )
    (net (code "46") (name "unconnected-(CN6-RX1--PadB10)") (class "Default")
      (node (ref "CN6") (pin "B10") (pinfunction "RX1-_B10") (pintype "passive+no_connect"))
    )
    (net (code "47") (name "unconnected-(CN6-RX2+-PadA11)") (class "Default")
      (node (ref "CN6") (pin "A11") (pinfunction "RX2+_A11") (pintype "passive+no_connect"))
    )
    (net (code "48") (name "unconnected-(CN6-RX2--PadA10)") (class "Default")
      (node (ref "CN6") (pin "A10") (pinfunction "RX2-_A10") (pintype "passive+no_connect"))
    )
    (net (code "49") (name "unconnected-(CN6-SBU1-PadA8)") (class "Default")
      (node (ref "CN6") (pin "A8") (pinfunction "SBU1_A8") (pintype "passive+no_connect"))
    )
    (net (code "50") (name "unconnected-(CN6-SBU2-PadB8)") (class "Default")
      (node (ref "CN6") (pin "B8") (pinfunction "SBU2_B8") (pintype "passive+no_connect"))
    )
    (net (code "51") (name "unconnected-(CN6-TX1+-PadA2)") (class "Default")
      (node (ref "CN6") (pin "A2") (pinfunction "TX1+_A2") (pintype "passive+no_connect"))
    )
    (net (code "52") (name "unconnected-(CN6-TX1--PadA3)") (class "Default")
      (node (ref "CN6") (pin "A3") (pinfunction "TX1-_A3") (pintype "passive+no_connect"))
    )
    (net (code "53") (name "unconnected-(CN6-TX2+-PadB2)") (class "Default")
      (node (ref "CN6") (pin "B2") (pinfunction "TX2+_B2") (pintype "passive+no_connect"))
    )
    (net (code "54") (name "unconnected-(CN6-TX2--PadB3)") (class "Default")
      (node (ref "CN6") (pin "B3") (pinfunction "TX2-_B3") (pintype "passive+no_connect"))
    )
    (net (code "55") (name "unconnected-(U4-BSTOUT-Pad34)") (class "Default")
      (node (ref "U4") (pin "34") (pinfunction "BSTOUT_34") (pintype "passive+no_connect"))
    )
    (net (code "56") (name "unconnected-(U4-SWOUT-Pad38)") (class "Default")
      (node (ref "U4") (pin "38") (pinfunction "SWOUT_38") (pintype "passive+no_connect"))
    )
    (net (code "57") (name "unconnected-(U4-VBUSOTG-Pad35)") (class "Default")
      (node (ref "U4") (pin "35") (pinfunction "VBUSOTG_35") (pintype "passive+no_connect"))
    )
  )
)
